# sigma_mix.net
KiCad netlist of a schematic drawn in EAGLE
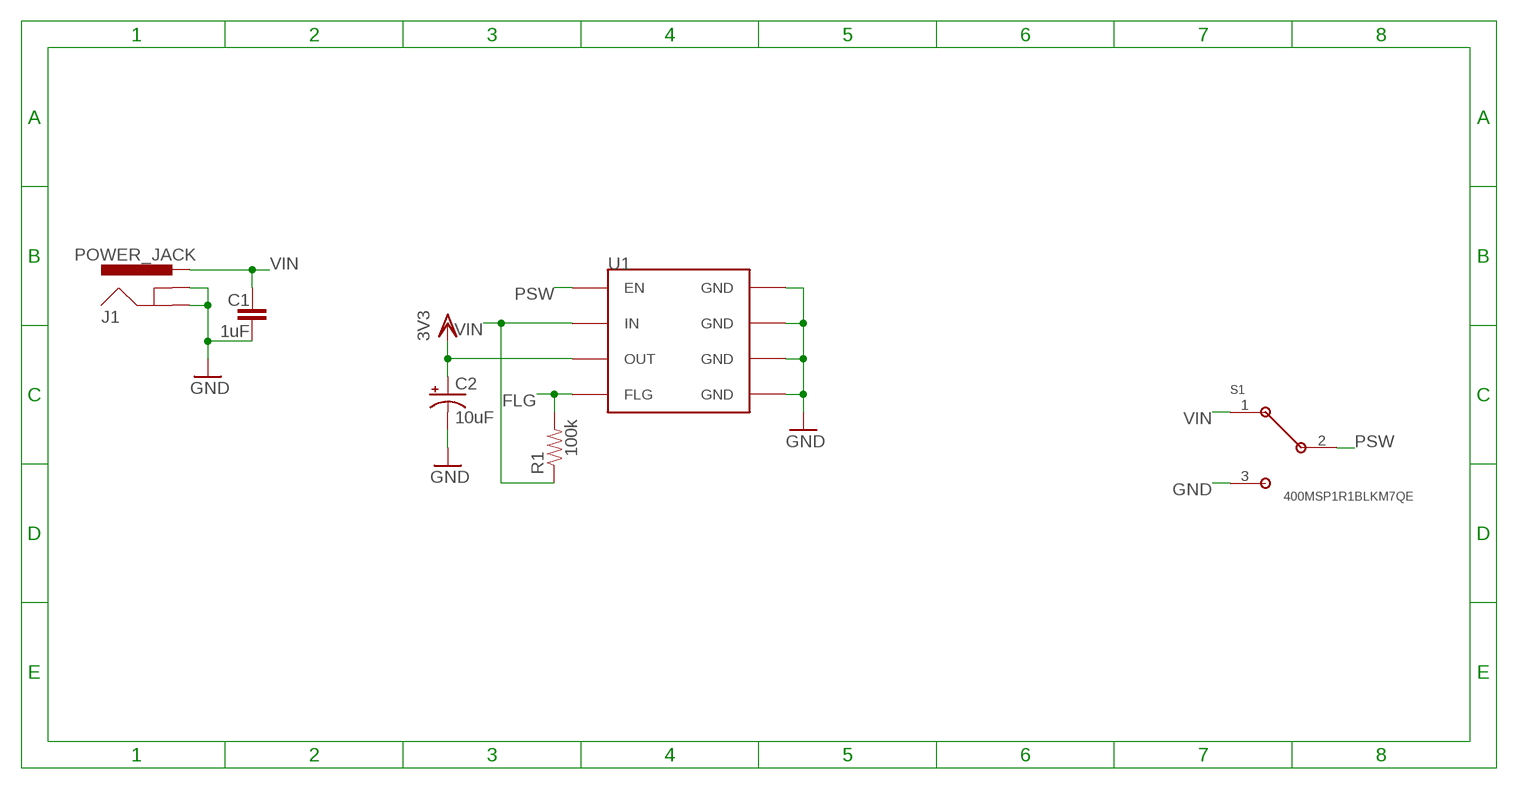
[diagram p0: schematic, sheet 1]
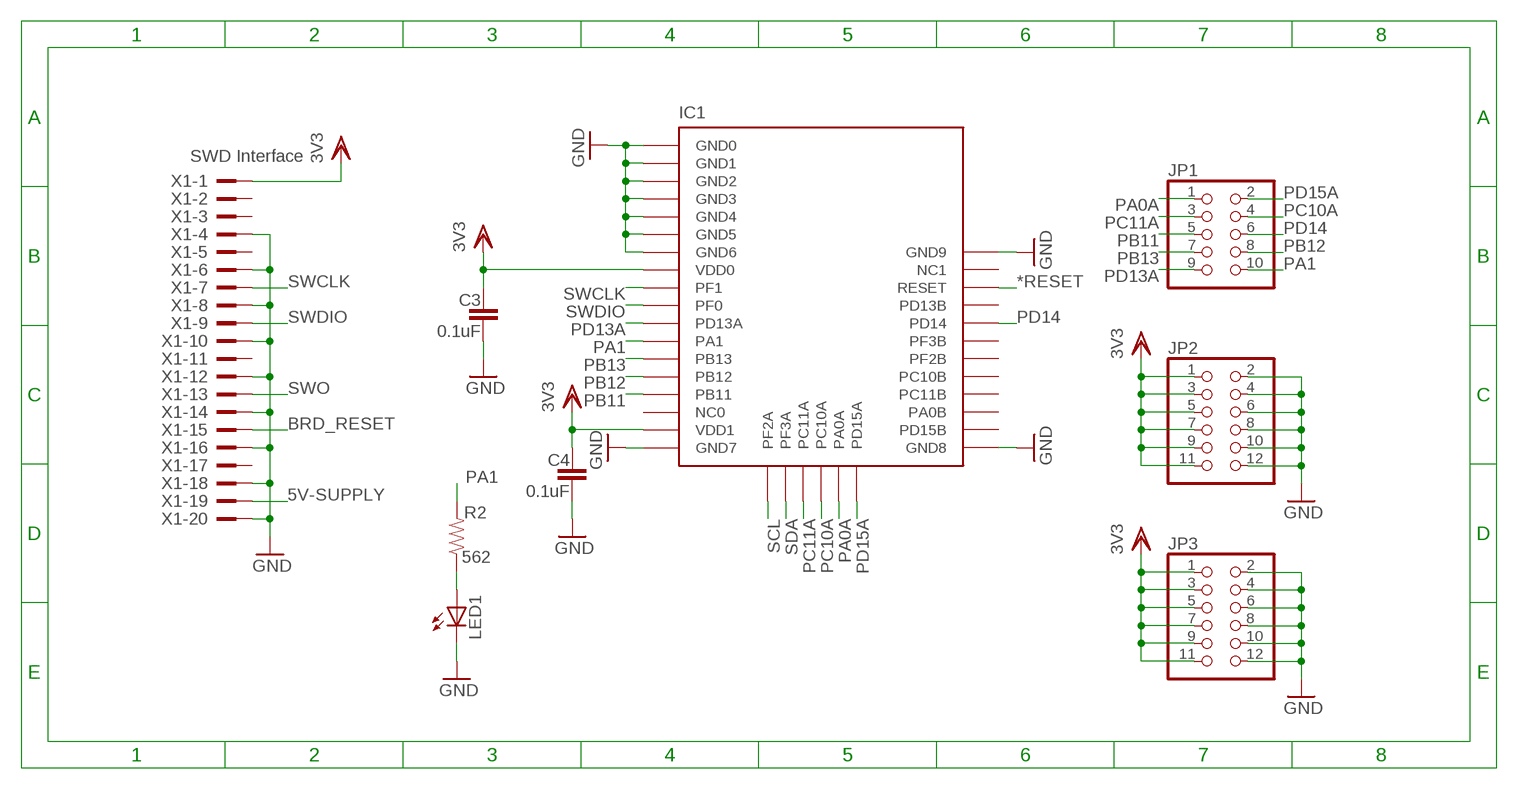
[diagram p1: schematic, sheet 2]
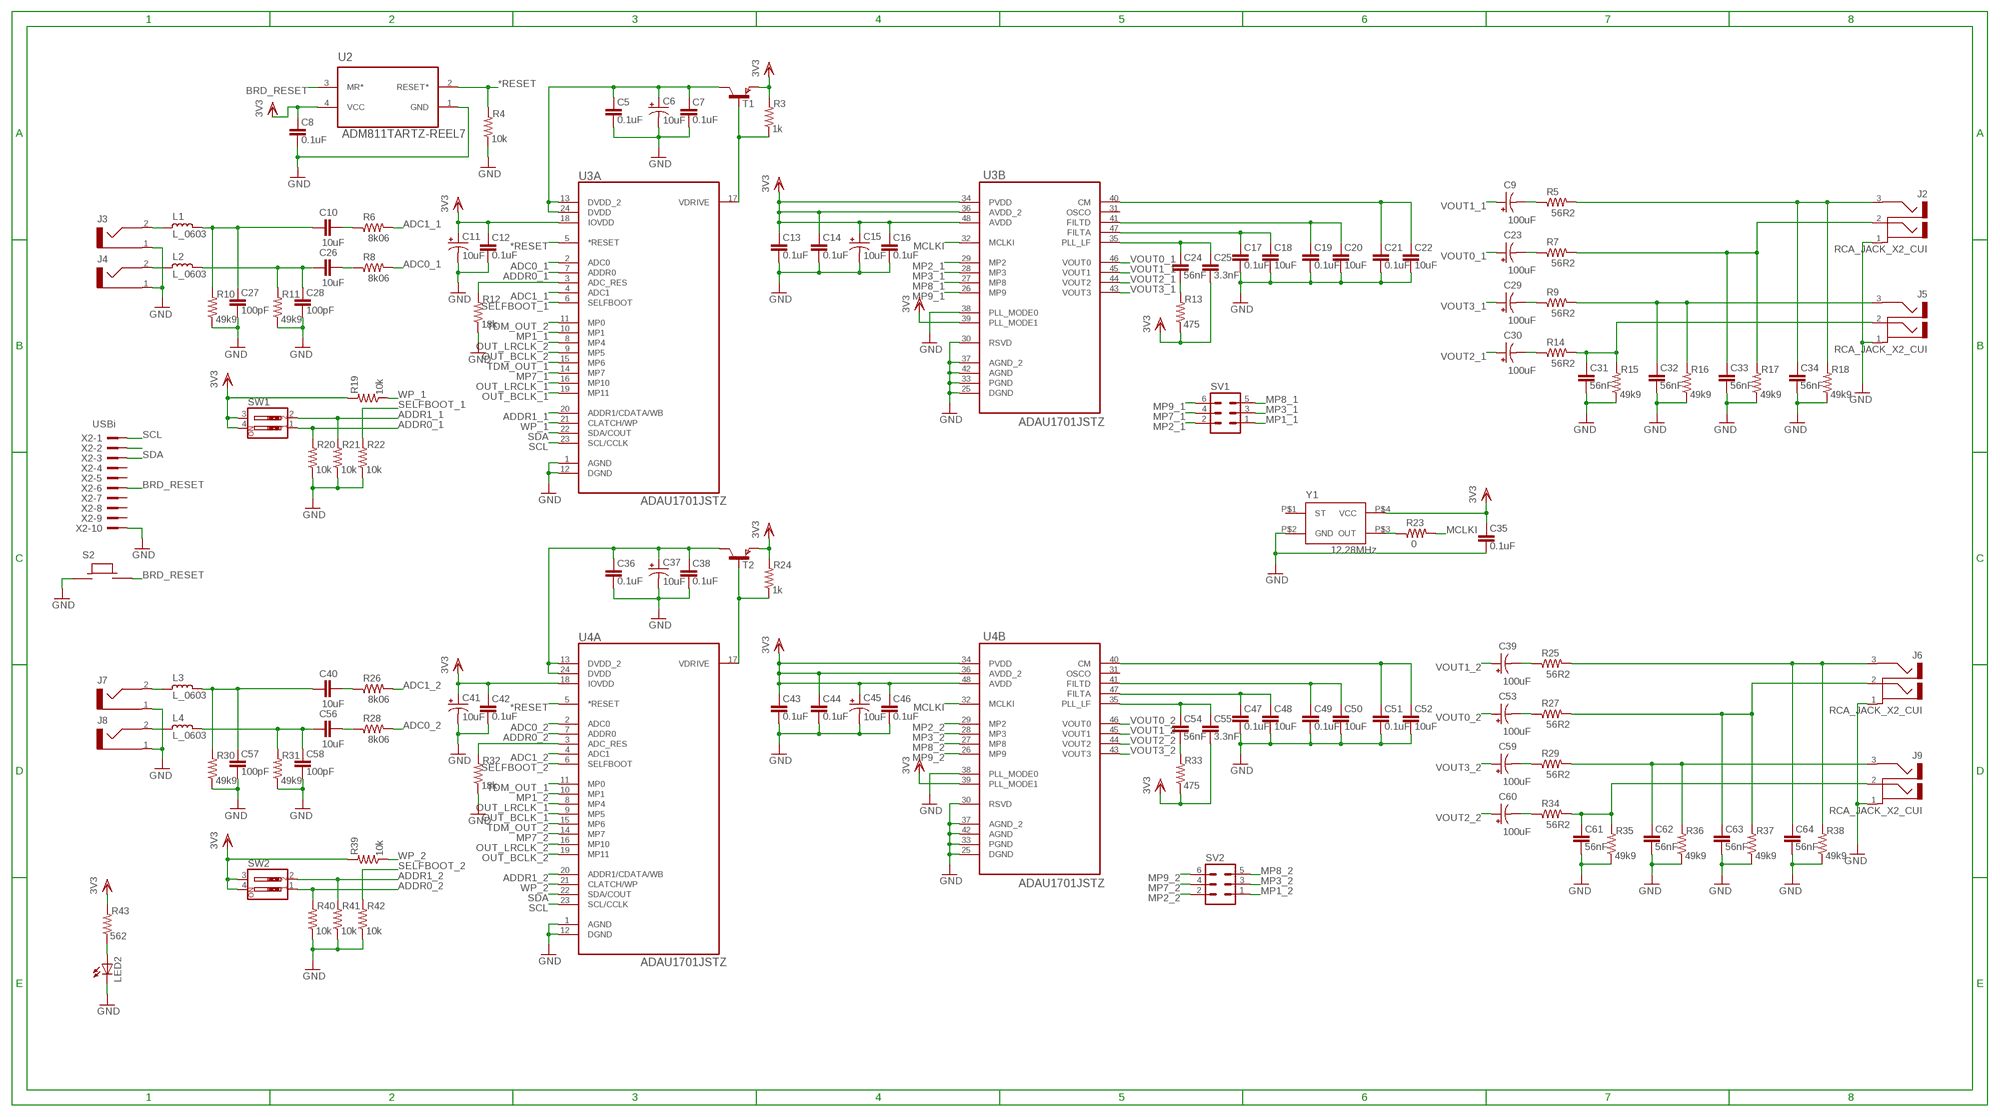
[diagram p2: schematic, sheet 3]

(export (version "E")
  (design (tool "Eeschema 10.0.6"))
  (components
    (comp (ref "C3")
      (value "0.1uF")
      (footprint "eagle-import:C2012")
      (libsource (lib "eagle-import") (part "C-EUC2012"))
    )
    (comp (ref "C4")
      (value "0.1uF")
      (footprint "eagle-import:C2012")
      (libsource (lib "eagle-import") (part "C-EUC2012"))
    )
    (comp (ref "IC1")
      (value "BGM113")
      (footprint "eagle-import:BLE113")
      (libsource (lib "eagle-import") (part "BGM113"))
    )
    (comp (ref "JP1")
      (value "PINHD-2X5")
      (footprint "eagle-import:2X05")
      (libsource (lib "eagle-import") (part "PINHD-2X5"))
    )
    (comp (ref "JP2")
      (value "PINHD-2X6")
      (footprint "eagle-import:2X06")
      (libsource (lib "eagle-import") (part "PINHD-2X6"))
    )
    (comp (ref "JP3")
      (value "PINHD-2X6")
      (footprint "eagle-import:2X06")
      (libsource (lib "eagle-import") (part "PINHD-2X6"))
    )
    (comp (ref "LED1")
      (value "LEDCHIPLED_1206")
      (footprint "eagle-import:CHIPLED_1206")
      (libsource (lib "eagle-import") (part "LEDCHIPLED_1206"))
    )
    (comp (ref "R2")
      (value "562")
      (footprint "eagle-import:0603-RES")
      (libsource (lib "eagle-import") (part "RESISTOR0603-RES"))
    )
    (comp (ref "X1")
      (value "SWD Interface")
      (footprint "eagle-import:PAK100_2500-20")
      (libsource (lib "eagle-import") (part "2520-"))
    )
    (comp (ref "C5")
      (value "0.1uF")
      (footprint "eagle-import:C2012")
      (libsource (lib "eagle-import") (part "C-EUC2012"))
    )
    (comp (ref "C6")
      (value "10uF")
      (footprint "eagle-import:R_2012-12R")
      (libsource (lib "eagle-import") (part "CPOL-USR/2012-12R"))
    )
    (comp (ref "C7")
      (value "0.1uF")
      (footprint "eagle-import:C2012")
      (libsource (lib "eagle-import") (part "C-EUC2012"))
    )
    (comp (ref "C8")
      (value "0.1uF")
      (footprint "eagle-import:C2012")
      (libsource (lib "eagle-import") (part "C-EUC2012"))
    )
    (comp (ref "C9")
      (value "100uF")
      (footprint "eagle-import:B_3528-21R")
      (libsource (lib "eagle-import") (part "CPOL-USB/3528-21R"))
    )
    (comp (ref "C10")
      (value "10uF")
      (footprint "eagle-import:C2012")
      (libsource (lib "eagle-import") (part "C-EUC2012"))
    )
    (comp (ref "C11")
      (value "10uF")
      (footprint "eagle-import:R_2012-12R")
      (libsource (lib "eagle-import") (part "CPOL-USR/2012-12R"))
    )
    (comp (ref "C12")
      (value "0.1uF")
      (footprint "eagle-import:C2012")
      (libsource (lib "eagle-import") (part "C-EUC2012"))
    )
    (comp (ref "C13")
      (value "0.1uF")
      (footprint "eagle-import:C2012")
      (libsource (lib "eagle-import") (part "C-EUC2012"))
    )
    (comp (ref "C14")
      (value "0.1uF")
      (footprint "eagle-import:C2012")
      (libsource (lib "eagle-import") (part "C-EUC2012"))
    )
    (comp (ref "C15")
      (value "10uF")
      (footprint "eagle-import:R_2012-12R")
      (libsource (lib "eagle-import") (part "CPOL-USR/2012-12R"))
    )
    (comp (ref "C16")
      (value "0.1uF")
      (footprint "eagle-import:C2012")
      (libsource (lib "eagle-import") (part "C-EUC2012"))
    )
    (comp (ref "C17")
      (value "0.1uF")
      (footprint "eagle-import:C2012")
      (libsource (lib "eagle-import") (part "C-EUC2012"))
    )
    (comp (ref "C18")
      (value "10uF")
      (footprint "eagle-import:C2012")
      (libsource (lib "eagle-import") (part "C-EUC2012"))
    )
    (comp (ref "C19")
      (value "0.1uF")
      (footprint "eagle-import:C2012")
      (libsource (lib "eagle-import") (part "C-EUC2012"))
    )
    (comp (ref "C20")
      (value "10uF")
      (footprint "eagle-import:C2012")
      (libsource (lib "eagle-import") (part "C-EUC2012"))
    )
    (comp (ref "C21")
      (value "0.1uF")
      (footprint "eagle-import:C2012")
      (libsource (lib "eagle-import") (part "C-EUC2012"))
    )
    (comp (ref "C22")
      (value "10uF")
      (footprint "eagle-import:C2012")
      (libsource (lib "eagle-import") (part "C-EUC2012"))
    )
    (comp (ref "C23")
      (value "100uF")
      (footprint "eagle-import:B_3528-21R")
      (libsource (lib "eagle-import") (part "CPOL-USB/3528-21R"))
    )
    (comp (ref "C24")
      (value "56nF")
      (footprint "eagle-import:C2012")
      (libsource (lib "eagle-import") (part "C-EUC2012"))
    )
    (comp (ref "C25")
      (value "3.3nF")
      (footprint "eagle-import:C2012")
      (libsource (lib "eagle-import") (part "C-EUC2012"))
    )
    (comp (ref "C26")
      (value "10uF")
      (footprint "eagle-import:C2012")
      (libsource (lib "eagle-import") (part "C-EUC2012"))
    )
    (comp (ref "C27")
      (value "100pF")
      (footprint "eagle-import:C2012")
      (libsource (lib "eagle-import") (part "C-EUC2012"))
    )
    (comp (ref "C28")
      (value "100pF")
      (footprint "eagle-import:C2012")
      (libsource (lib "eagle-import") (part "C-EUC2012"))
    )
    (comp (ref "C29")
      (value "100uF")
      (footprint "eagle-import:B_3528-21R")
      (libsource (lib "eagle-import") (part "CPOL-USB/3528-21R"))
    )
    (comp (ref "C30")
      (value "100uF")
      (footprint "eagle-import:B_3528-21R")
      (libsource (lib "eagle-import") (part "CPOL-USB/3528-21R"))
    )
    (comp (ref "C31")
      (value "56nF")
      (footprint "eagle-import:C2012")
      (libsource (lib "eagle-import") (part "C-EUC2012"))
    )
    (comp (ref "C32")
      (value "56nF")
      (footprint "eagle-import:C2012")
      (libsource (lib "eagle-import") (part "C-EUC2012"))
    )
    (comp (ref "C33")
      (value "56nF")
      (footprint "eagle-import:C2012")
      (libsource (lib "eagle-import") (part "C-EUC2012"))
    )
    (comp (ref "C34")
      (value "56nF")
      (footprint "eagle-import:C2012")
      (libsource (lib "eagle-import") (part "C-EUC2012"))
    )
    (comp (ref "C35")
      (value "0.1uF")
      (footprint "eagle-import:C2012")
      (libsource (lib "eagle-import") (part "C-EUC2012"))
    )
    (comp (ref "C36")
      (value "0.1uF")
      (footprint "eagle-import:C2012")
      (libsource (lib "eagle-import") (part "C-EUC2012"))
    )
    (comp (ref "C37")
      (value "10uF")
      (footprint "eagle-import:R_2012-12R")
      (libsource (lib "eagle-import") (part "CPOL-USR/2012-12R"))
    )
    (comp (ref "C38")
      (value "0.1uF")
      (footprint "eagle-import:C2012")
      (libsource (lib "eagle-import") (part "C-EUC2012"))
    )
    (comp (ref "C39")
      (value "100uF")
      (footprint "eagle-import:B_3528-21R")
      (libsource (lib "eagle-import") (part "CPOL-USB/3528-21R"))
    )
    (comp (ref "C40")
      (value "10uF")
      (footprint "eagle-import:C2012")
      (libsource (lib "eagle-import") (part "C-EUC2012"))
    )
    (comp (ref "C41")
      (value "10uF")
      (footprint "eagle-import:R_2012-12R")
      (libsource (lib "eagle-import") (part "CPOL-USR/2012-12R"))
    )
    (comp (ref "C42")
      (value "0.1uF")
      (footprint "eagle-import:C2012")
      (libsource (lib "eagle-import") (part "C-EUC2012"))
    )
    (comp (ref "C43")
      (value "0.1uF")
      (footprint "eagle-import:C2012")
      (libsource (lib "eagle-import") (part "C-EUC2012"))
    )
    (comp (ref "C44")
      (value "0.1uF")
      (footprint "eagle-import:C2012")
      (libsource (lib "eagle-import") (part "C-EUC2012"))
    )
    (comp (ref "C45")
      (value "10uF")
      (footprint "eagle-import:R_2012-12R")
      (libsource (lib "eagle-import") (part "CPOL-USR/2012-12R"))
    )
    (comp (ref "C46")
      (value "0.1uF")
      (footprint "eagle-import:C2012")
      (libsource (lib "eagle-import") (part "C-EUC2012"))
    )
    (comp (ref "C47")
      (value "0.1uF")
      (footprint "eagle-import:C2012")
      (libsource (lib "eagle-import") (part "C-EUC2012"))
    )
    (comp (ref "C48")
      (value "10uF")
      (footprint "eagle-import:C2012")
      (libsource (lib "eagle-import") (part "C-EUC2012"))
    )
    (comp (ref "C49")
      (value "0.1uF")
      (footprint "eagle-import:C2012")
      (libsource (lib "eagle-import") (part "C-EUC2012"))
    )
    (comp (ref "C50")
      (value "10uF")
      (footprint "eagle-import:C2012")
      (libsource (lib "eagle-import") (part "C-EUC2012"))
    )
    (comp (ref "C51")
      (value "0.1uF")
      (footprint "eagle-import:C2012")
      (libsource (lib "eagle-import") (part "C-EUC2012"))
    )
    (comp (ref "C52")
      (value "10uF")
      (footprint "eagle-import:C2012")
      (libsource (lib "eagle-import") (part "C-EUC2012"))
    )
    (comp (ref "C53")
      (value "100uF")
      (footprint "eagle-import:B_3528-21R")
      (libsource (lib "eagle-import") (part "CPOL-USB/3528-21R"))
    )
    (comp (ref "C54")
      (value "56nF")
      (footprint "eagle-import:C2012")
      (libsource (lib "eagle-import") (part "C-EUC2012"))
    )
    (comp (ref "C55")
      (value "3.3nF")
      (footprint "eagle-import:C2012")
      (libsource (lib "eagle-import") (part "C-EUC2012"))
    )
    (comp (ref "C56")
      (value "10uF")
      (footprint "eagle-import:C2012")
      (libsource (lib "eagle-import") (part "C-EUC2012"))
    )
    (comp (ref "C57")
      (value "100pF")
      (footprint "eagle-import:C2012")
      (libsource (lib "eagle-import") (part "C-EUC2012"))
    )
    (comp (ref "C58")
      (value "100pF")
      (footprint "eagle-import:C2012")
      (libsource (lib "eagle-import") (part "C-EUC2012"))
    )
    (comp (ref "C59")
      (value "100uF")
      (footprint "eagle-import:B_3528-21R")
      (libsource (lib "eagle-import") (part "CPOL-USB/3528-21R"))
    )
    (comp (ref "C60")
      (value "100uF")
      (footprint "eagle-import:B_3528-21R")
      (libsource (lib "eagle-import") (part "CPOL-USB/3528-21R"))
    )
    (comp (ref "C61")
      (value "56nF")
      (footprint "eagle-import:C2012")
      (libsource (lib "eagle-import") (part "C-EUC2012"))
    )
    (comp (ref "C62")
      (value "56nF")
      (footprint "eagle-import:C2012")
      (libsource (lib "eagle-import") (part "C-EUC2012"))
    )
    (comp (ref "C63")
      (value "56nF")
      (footprint "eagle-import:C2012")
      (libsource (lib "eagle-import") (part "C-EUC2012"))
    )
    (comp (ref "C64")
      (value "56nF")
      (footprint "eagle-import:C2012")
      (libsource (lib "eagle-import") (part "C-EUC2012"))
    )
    (comp (ref "J2")
      (value "RCA_JACK_X2_CUI")
      (footprint "eagle-import:RCA_JACK_X2_CUI")
      (libsource (lib "eagle-import") (part "RCA_JACK_X2_CUI"))
    )
    (comp (ref "J3")
      (value "RCA_JACK_CUI")
      (footprint "eagle-import:RCA_JACK_CUI")
      (libsource (lib "eagle-import") (part "RCA_JACK_CUI"))
    )
    (comp (ref "J4")
      (value "RCA_JACK_CUI")
      (footprint "eagle-import:RCA_JACK_CUI")
      (libsource (lib "eagle-import") (part "RCA_JACK_CUI"))
    )
    (comp (ref "J5")
      (value "RCA_JACK_X2_CUI")
      (footprint "eagle-import:RCA_JACK_X2_CUI")
      (libsource (lib "eagle-import") (part "RCA_JACK_X2_CUI"))
    )
    (comp (ref "J6")
      (value "RCA_JACK_X2_CUI")
      (footprint "eagle-import:RCA_JACK_X2_CUI")
      (libsource (lib "eagle-import") (part "RCA_JACK_X2_CUI"))
    )
    (comp (ref "J7")
      (value "RCA_JACK_CUI")
      (footprint "eagle-import:RCA_JACK_CUI")
      (libsource (lib "eagle-import") (part "RCA_JACK_CUI"))
    )
    (comp (ref "J8")
      (value "RCA_JACK_CUI")
      (footprint "eagle-import:RCA_JACK_CUI")
      (libsource (lib "eagle-import") (part "RCA_JACK_CUI"))
    )
    (comp (ref "J9")
      (value "RCA_JACK_X2_CUI")
      (footprint "eagle-import:RCA_JACK_X2_CUI")
      (libsource (lib "eagle-import") (part "RCA_JACK_X2_CUI"))
    )
    (comp (ref "L1")
      (value "L_0603")
      (footprint "eagle-import:L0603")
      (libsource (lib "eagle-import") (part "L_0603"))
    )
    (comp (ref "L2")
      (value "L_0603")
      (footprint "eagle-import:L0603")
      (libsource (lib "eagle-import") (part "L_0603"))
    )
    (comp (ref "L3")
      (value "L_0603")
      (footprint "eagle-import:L0603")
      (libsource (lib "eagle-import") (part "L_0603"))
    )
    (comp (ref "L4")
      (value "L_0603")
      (footprint "eagle-import:L0603")
      (libsource (lib "eagle-import") (part "L_0603"))
    )
    (comp (ref "LED2")
      (value "LEDCHIPLED_1206")
      (footprint "eagle-import:CHIPLED_1206")
      (libsource (lib "eagle-import") (part "LEDCHIPLED_1206"))
    )
    (comp (ref "R3")
      (value "1k")
      (footprint "eagle-import:0603-RES")
      (libsource (lib "eagle-import") (part "RESISTOR0603-RES"))
    )
    (comp (ref "R4")
      (value "10k")
      (footprint "eagle-import:0603-RES")
      (libsource (lib "eagle-import") (part "RESISTOR0603-RES"))
    )
    (comp (ref "R5")
      (value "56R2")
      (footprint "eagle-import:0603-RES")
      (libsource (lib "eagle-import") (part "RESISTOR0603-RES"))
    )
    (comp (ref "R6")
      (value "8k06")
      (footprint "eagle-import:0603-RES")
      (libsource (lib "eagle-import") (part "RESISTOR0603-RES"))
    )
    (comp (ref "R7")
      (value "56R2")
      (footprint "eagle-import:0603-RES")
      (libsource (lib "eagle-import") (part "RESISTOR0603-RES"))
    )
    (comp (ref "R8")
      (value "8k06")
      (footprint "eagle-import:0603-RES")
      (libsource (lib "eagle-import") (part "RESISTOR0603-RES"))
    )
    (comp (ref "R9")
      (value "56R2")
      (footprint "eagle-import:0603-RES")
      (libsource (lib "eagle-import") (part "RESISTOR0603-RES"))
    )
    (comp (ref "R10")
      (value "49k9")
      (footprint "eagle-import:0603-RES")
      (libsource (lib "eagle-import") (part "RESISTOR0603-RES"))
    )
    (comp (ref "R11")
      (value "49k9")
      (footprint "eagle-import:0603-RES")
      (libsource (lib "eagle-import") (part "RESISTOR0603-RES"))
    )
    (comp (ref "R12")
      (value "18k")
      (footprint "eagle-import:0603-RES")
      (libsource (lib "eagle-import") (part "RESISTOR0603-RES"))
    )
    (comp (ref "R13")
      (value "475")
      (footprint "eagle-import:0603-RES")
      (libsource (lib "eagle-import") (part "RESISTOR0603-RES"))
    )
    (comp (ref "R14")
      (value "56R2")
      (footprint "eagle-import:0603-RES")
      (libsource (lib "eagle-import") (part "RESISTOR0603-RES"))
    )
    (comp (ref "R15")
      (value "49k9")
      (footprint "eagle-import:0603-RES")
      (libsource (lib "eagle-import") (part "RESISTOR0603-RES"))
    )
    (comp (ref "R16")
      (value "49k9")
      (footprint "eagle-import:0603-RES")
      (libsource (lib "eagle-import") (part "RESISTOR0603-RES"))
    )
    (comp (ref "R17")
      (value "49k9")
      (footprint "eagle-import:0603-RES")
      (libsource (lib "eagle-import") (part "RESISTOR0603-RES"))
    )
    (comp (ref "R18")
      (value "49k9")
      (footprint "eagle-import:0603-RES")
      (libsource (lib "eagle-import") (part "RESISTOR0603-RES"))
    )
    (comp (ref "R19")
      (value "10k")
      (footprint "eagle-import:0603-RES")
      (libsource (lib "eagle-import") (part "RESISTOR0603-RES"))
    )
    (comp (ref "R20")
      (value "10k")
      (footprint "eagle-import:0603-RES")
      (libsource (lib "eagle-import") (part "RESISTOR0603-RES"))
    )
    (comp (ref "R21")
      (value "10k")
      (footprint "eagle-import:0603-RES")
      (libsource (lib "eagle-import") (part "RESISTOR0603-RES"))
    )
    (comp (ref "R22")
      (value "10k")
      (footprint "eagle-import:0603-RES")
      (libsource (lib "eagle-import") (part "RESISTOR0603-RES"))
    )
    (comp (ref "R23")
      (value "0")
      (footprint "eagle-import:0603-RES")
      (libsource (lib "eagle-import") (part "RESISTOR0603-RES"))
    )
    (comp (ref "R24")
      (value "1k")
      (footprint "eagle-import:0603-RES")
      (libsource (lib "eagle-import") (part "RESISTOR0603-RES"))
    )
    (comp (ref "R25")
      (value "56R2")
      (footprint "eagle-import:0603-RES")
      (libsource (lib "eagle-import") (part "RESISTOR0603-RES"))
    )
    (comp (ref "R26")
      (value "8k06")
      (footprint "eagle-import:0603-RES")
      (libsource (lib "eagle-import") (part "RESISTOR0603-RES"))
    )
    (comp (ref "R27")
      (value "56R2")
      (footprint "eagle-import:0603-RES")
      (libsource (lib "eagle-import") (part "RESISTOR0603-RES"))
    )
    (comp (ref "R28")
      (value "8k06")
      (footprint "eagle-import:0603-RES")
      (libsource (lib "eagle-import") (part "RESISTOR0603-RES"))
    )
    (comp (ref "R29")
      (value "56R2")
      (footprint "eagle-import:0603-RES")
      (libsource (lib "eagle-import") (part "RESISTOR0603-RES"))
    )
    (comp (ref "R30")
      (value "49k9")
      (footprint "eagle-import:0603-RES")
      (libsource (lib "eagle-import") (part "RESISTOR0603-RES"))
    )
    (comp (ref "R31")
      (value "49k9")
      (footprint "eagle-import:0603-RES")
      (libsource (lib "eagle-import") (part "RESISTOR0603-RES"))
    )
    (comp (ref "R32")
      (value "18k")
      (footprint "eagle-import:0603-RES")
      (libsource (lib "eagle-import") (part "RESISTOR0603-RES"))
    )
    (comp (ref "R33")
      (value "475")
      (footprint "eagle-import:0603-RES")
      (libsource (lib "eagle-import") (part "RESISTOR0603-RES"))
    )
    (comp (ref "R34")
      (value "56R2")
      (footprint "eagle-import:0603-RES")
      (libsource (lib "eagle-import") (part "RESISTOR0603-RES"))
    )
    (comp (ref "R35")
      (value "49k9")
      (footprint "eagle-import:0603-RES")
      (libsource (lib "eagle-import") (part "RESISTOR0603-RES"))
    )
    (comp (ref "R36")
      (value "49k9")
      (footprint "eagle-import:0603-RES")
      (libsource (lib "eagle-import") (part "RESISTOR0603-RES"))
    )
    (comp (ref "R37")
      (value "49k9")
      (footprint "eagle-import:0603-RES")
      (libsource (lib "eagle-import") (part "RESISTOR0603-RES"))
    )
    (comp (ref "R38")
      (value "49k9")
      (footprint "eagle-import:0603-RES")
      (libsource (lib "eagle-import") (part "RESISTOR0603-RES"))
    )
    (comp (ref "R39")
      (value "10k")
      (footprint "eagle-import:0603-RES")
      (libsource (lib "eagle-import") (part "RESISTOR0603-RES"))
    )
    (comp (ref "R40")
      (value "10k")
      (footprint "eagle-import:0603-RES")
      (libsource (lib "eagle-import") (part "RESISTOR0603-RES"))
    )
    (comp (ref "R41")
      (value "10k")
      (footprint "eagle-import:0603-RES")
      (libsource (lib "eagle-import") (part "RESISTOR0603-RES"))
    )
    (comp (ref "R42")
      (value "10k")
      (footprint "eagle-import:0603-RES")
      (libsource (lib "eagle-import") (part "RESISTOR0603-RES"))
    )
    (comp (ref "R43")
      (value "562")
      (footprint "eagle-import:0603-RES")
      (libsource (lib "eagle-import") (part "RESISTOR0603-RES"))
    )
    (comp (ref "S2")
      (value "OMRON_B3M")
      (footprint "eagle-import:OMRON_B3M")
      (libsource (lib "eagle-import") (part "OMRON_B3M"))
    )
    (comp (ref "SV1")
      (value "MA03-2")
      (footprint "eagle-import:MA03-2")
      (libsource (lib "eagle-import") (part "MA03-2"))
    )
    (comp (ref "SV2")
      (value "MA03-2")
      (footprint "eagle-import:MA03-2")
      (libsource (lib "eagle-import") (part "MA03-2"))
    )
    (comp (ref "SW1")
      (value "SW_DIP-2")
      (footprint "eagle-import:EDG-02")
      (libsource (lib "eagle-import") (part "SW_DIP-2"))
    )
    (comp (ref "SW2")
      (value "SW_DIP-2")
      (footprint "eagle-import:EDG-02")
      (libsource (lib "eagle-import") (part "SW_DIP-2"))
    )
    (comp (ref "T1")
      (value "PNPSOT23")
      (footprint "eagle-import:SOT-23")
      (fields (field (name "MPN") "DSS20200L-7"))
      (libsource (lib "eagle-import") (part "PNPSOT23"))
    )
    (comp (ref "T2")
      (value "PNPSOT23")
      (footprint "eagle-import:SOT-23")
      (fields (field (name "MPN") "DSS20200L-7"))
      (libsource (lib "eagle-import") (part "PNPSOT23"))
    )
    (comp (ref "U2")
      (value "ADM811TARTZ-REEL7")
      (footprint "eagle-import:SOT143P290X130-4N")
      (libsource (lib "eagle-import") (part "ADM811TARTZ-REEL7"))
    )
    (comp (ref "U3")
      (value "ADAU1701JSTZ")
      (footprint "eagle-import:QFP50P900X900X160-48N")
      (libsource (lib "eagle-import") (part "ADAU1701JSTZ"))
    )
    (comp (ref "U4")
      (value "ADAU1701JSTZ")
      (footprint "eagle-import:QFP50P900X900X160-48N")
      (libsource (lib "eagle-import") (part "ADAU1701JSTZ"))
    )
    (comp (ref "X2")
      (value "USBi")
      (footprint "eagle-import:PAK100_2500-10")
      (fields (field (name "MF") "3M") (field (name "MPN") "2510-6002UB"))
      (libsource (lib "eagle-import") (part "2510-"))
    )
    (comp (ref "Y1")
      (value "12.28MHz")
      (footprint "eagle-import:SG-210")
      (libsource (lib "eagle-import") (part "XTAL-OSC"))
    )
    (comp (ref "C1")
      (value "1uF")
      (footprint "eagle-import:C2012")
      (libsource (lib "eagle-import") (part "C-EUC2012"))
    )
    (comp (ref "C2")
      (value "10uF")
      (footprint "eagle-import:R_2012-12R")
      (libsource (lib "eagle-import") (part "CPOL-USR/2012-12R"))
    )
    (comp (ref "J1")
      (value "POWER_JACK")
      (footprint "eagle-import:POWER_JACK_PTH_LOCK")
      (libsource (lib "eagle-import") (part "POWER_JACKPTH_LOCK"))
    )
    (comp (ref "R1")
      (value "100k")
      (footprint "eagle-import:0603-RES")
      (libsource (lib "eagle-import") (part "RESISTOR0603-RES"))
    )
    (comp (ref "S1")
      (value "400MSP1R1BLKM7QE")
      (footprint "eagle-import:400MSP1R1BLKM7QE")
      (libsource (lib "eagle-import") (part "400MSP1R1BLKM7QE"))
    )
    (comp (ref "U1")
      (value "MIC39100")
      (footprint "eagle-import:SOIC8")
      (libsource (lib "eagle-import") (part "MIC39100"))
    )
  )
  (nets
    (net (code "1") (name "*RESET") (class "Default")
      (node (ref "IC1") (pin "P$34") (pinfunction "RESET_P$34") (pintype "input"))
      (node (ref "R4") (pin "2") (pinfunction "2_2") (pintype "passive"))
      (node (ref "U2") (pin "2") (pinfunction "RESET*_2") (pintype "passive"))
      (node (ref "U3") (pin "5") (pinfunction "*RESET_5") (pintype "input"))
      (node (ref "U4") (pin "5") (pinfunction "*RESET_5") (pintype "input"))
    )
    (net (code "2") (name "5V-SUPPLY") (class "Default")
      (node (ref "X1") (pin "19") (pinfunction "KL_19") (pintype "passive"))
    )
    (net (code "3") (name "ADC0_1") (class "Default")
      (node (ref "R8") (pin "2") (pinfunction "2_2") (pintype "passive"))
      (node (ref "U3") (pin "2") (pinfunction "ADC0_2") (pintype "input"))
    )
    (net (code "4") (name "ADC0_2") (class "Default")
      (node (ref "R28") (pin "2") (pinfunction "2_2") (pintype "passive"))
      (node (ref "U4") (pin "2") (pinfunction "ADC0_2") (pintype "input"))
    )
    (net (code "5") (name "ADC1_1") (class "Default")
      (node (ref "R6") (pin "2") (pinfunction "2_2") (pintype "passive"))
      (node (ref "U3") (pin "4") (pinfunction "ADC1_4") (pintype "input"))
    )
    (net (code "6") (name "ADC1_2") (class "Default")
      (node (ref "R26") (pin "2") (pinfunction "2_2") (pintype "passive"))
      (node (ref "U4") (pin "4") (pinfunction "ADC1_4") (pintype "input"))
    )
    (net (code "7") (name "ADDR0_1") (class "Default")
      (node (ref "R20") (pin "2") (pinfunction "2_2") (pintype "passive"))
      (node (ref "SW1") (pin "1") (pinfunction "1_1") (pintype "passive"))
      (node (ref "U3") (pin "7") (pinfunction "ADDR0_7") (pintype "input"))
    )
    (net (code "8") (name "ADDR0_2") (class "Default")
      (node (ref "R40") (pin "2") (pinfunction "2_2") (pintype "passive"))
      (node (ref "SW2") (pin "1") (pinfunction "1_1") (pintype "passive"))
      (node (ref "U4") (pin "7") (pinfunction "ADDR0_7") (pintype "input"))
    )
    (net (code "9") (name "ADDR1_1") (class "Default")
      (node (ref "R21") (pin "2") (pinfunction "2_2") (pintype "passive"))
      (node (ref "SW1") (pin "2") (pinfunction "2_2") (pintype "passive"))
      (node (ref "U3") (pin "20") (pinfunction "ADDR1/CDATA/WB_20") (pintype "input"))
    )
    (net (code "10") (name "ADDR1_2") (class "Default")
      (node (ref "R41") (pin "2") (pinfunction "2_2") (pintype "passive"))
      (node (ref "SW2") (pin "2") (pinfunction "2_2") (pintype "passive"))
      (node (ref "U4") (pin "20") (pinfunction "ADDR1/CDATA/WB_20") (pintype "input"))
    )
    (net (code "11") (name "BRD_RESET") (class "Default")
      (node (ref "S2") (pin "P$2") (pinfunction "P$2_P$2") (pintype "bidirectional"))
      (node (ref "U2") (pin "3") (pinfunction "MR*_3") (pintype "passive"))
      (node (ref "X1") (pin "15") (pinfunction "KL_15") (pintype "passive"))
      (node (ref "X2") (pin "6") (pinfunction "KL_6") (pintype "passive"))
    )
    (net (code "12") (name "FLG") (class "Default")
      (node (ref "R1") (pin "2") (pinfunction "2_2") (pintype "passive"))
      (node (ref "U1") (pin "4") (pinfunction "FLG_4") (pintype "output"))
    )
    (net (code "13") (name "GND") (class "Default")
      (node (ref "C1") (pin "2") (pinfunction "2_2") (pintype "passive"))
      (node (ref "C11") (pin "-") (pinfunction "-_-") (pintype "passive"))
      (node (ref "C12") (pin "2") (pinfunction "2_2") (pintype "passive"))
      (node (ref "C13") (pin "2") (pinfunction "2_2") (pintype "passive"))
      (node (ref "C14") (pin "2") (pinfunction "2_2") (pintype "passive"))
      (node (ref "C15") (pin "-") (pinfunction "-_-") (pintype "passive"))
      (node (ref "C16") (pin "2") (pinfunction "2_2") (pintype "passive"))
      (node (ref "C17") (pin "2") (pinfunction "2_2") (pintype "passive"))
      (node (ref "C18") (pin "2") (pinfunction "2_2") (pintype "passive"))
      (node (ref "C19") (pin "2") (pinfunction "2_2") (pintype "passive"))
      (node (ref "C2") (pin "-") (pinfunction "-_-") (pintype "passive"))
      (node (ref "C20") (pin "2") (pinfunction "2_2") (pintype "passive"))
      (node (ref "C21") (pin "2") (pinfunction "2_2") (pintype "passive"))
      (node (ref "C22") (pin "2") (pinfunction "2_2") (pintype "passive"))
      (node (ref "C27") (pin "2") (pinfunction "2_2") (pintype "passive"))
      (node (ref "C28") (pin "2") (pinfunction "2_2") (pintype "passive"))
      (node (ref "C3") (pin "2") (pinfunction "2_2") (pintype "passive"))
      (node (ref "C31") (pin "2") (pinfunction "2_2") (pintype "passive"))
      (node (ref "C32") (pin "2") (pinfunction "2_2") (pintype "passive"))
      (node (ref "C33") (pin "2") (pinfunction "2_2") (pintype "passive"))
      (node (ref "C34") (pin "2") (pinfunction "2_2") (pintype "passive"))
      (node (ref "C35") (pin "2") (pinfunction "2_2") (pintype "passive"))
      (node (ref "C36") (pin "2") (pinfunction "2_2") (pintype "passive"))
      (node (ref "C37") (pin "-") (pinfunction "-_-") (pintype "passive"))
      (node (ref "C38") (pin "2") (pinfunction "2_2") (pintype "passive"))
      (node (ref "C4") (pin "2") (pinfunction "2_2") (pintype "passive"))
      (node (ref "C41") (pin "-") (pinfunction "-_-") (pintype "passive"))
      (node (ref "C42") (pin "2") (pinfunction "2_2") (pintype "passive"))
      (node (ref "C43") (pin "2") (pinfunction "2_2") (pintype "passive"))
      (node (ref "C44") (pin "2") (pinfunction "2_2") (pintype "passive"))
      (node (ref "C45") (pin "-") (pinfunction "-_-") (pintype "passive"))
      (node (ref "C46") (pin "2") (pinfunction "2_2") (pintype "passive"))
      (node (ref "C47") (pin "2") (pinfunction "2_2") (pintype "passive"))
      (node (ref "C48") (pin "2") (pinfunction "2_2") (pintype "passive"))
      (node (ref "C49") (pin "2") (pinfunction "2_2") (pintype "passive"))
      (node (ref "C5") (pin "2") (pinfunction "2_2") (pintype "passive"))
      (node (ref "C50") (pin "2") (pinfunction "2_2") (pintype "passive"))
      (node (ref "C51") (pin "2") (pinfunction "2_2") (pintype "passive"))
      (node (ref "C52") (pin "2") (pinfunction "2_2") (pintype "passive"))
      (node (ref "C57") (pin "2") (pinfunction "2_2") (pintype "passive"))
      (node (ref "C58") (pin "2") (pinfunction "2_2") (pintype "passive"))
      (node (ref "C6") (pin "-") (pinfunction "-_-") (pintype "passive"))
      (node (ref "C61") (pin "2") (pinfunction "2_2") (pintype "passive"))
      (node (ref "C62") (pin "2") (pinfunction "2_2") (pintype "passive"))
      (node (ref "C63") (pin "2") (pinfunction "2_2") (pintype "passive"))
      (node (ref "C64") (pin "2") (pinfunction "2_2") (pintype "passive"))
      (node (ref "C7") (pin "2") (pinfunction "2_2") (pintype "passive"))
      (node (ref "C8") (pin "2") (pinfunction "2_2") (pintype "passive"))
      (node (ref "IC1") (pin "P$1") (pinfunction "GND0_P$1") (pintype "power_in"))
      (node (ref "IC1") (pin "P$18") (pinfunction "GND7_P$18") (pintype "power_in"))
      (node (ref "IC1") (pin "P$2") (pinfunction "GND1_P$2") (pintype "power_in"))
      (node (ref "IC1") (pin "P$25") (pinfunction "GND8_P$25") (pintype "power_in"))
      (node (ref "IC1") (pin "P$3") (pinfunction "GND2_P$3") (pintype "power_in"))
      (node (ref "IC1") (pin "P$36") (pinfunction "GND9_P$36") (pintype "power_in"))
      (node (ref "IC1") (pin "P$4") (pinfunction "GND3_P$4") (pintype "power_in"))
      (node (ref "IC1") (pin "P$5") (pinfunction "GND4_P$5") (pintype "power_in"))
      (node (ref "IC1") (pin "P$6") (pinfunction "GND5_P$6") (pintype "power_in"))
      (node (ref "IC1") (pin "P$7") (pinfunction "GND6_P$7") (pintype "power_in"))
      (node (ref "J1") (pin "GND") (pinfunction "GND_GND") (pintype "bidirectional"))
      (node (ref "J1") (pin "GNDBREAK") (pinfunction "GNDBREAK_GNDBREAK") (pintype "bidirectional"))
      (node (ref "J2") (pin "1") (pinfunction "1_1") (pintype "power_in"))
      (node (ref "J3") (pin "1") (pinfunction "1_1") (pintype "bidirectional"))
      (node (ref "J4") (pin "1") (pinfunction "1_1") (pintype "bidirectional"))
      (node (ref "J5") (pin "1") (pinfunction "1_1") (pintype "power_in"))
      (node (ref "J6") (pin "1") (pinfunction "1_1") (pintype "power_in"))
      (node (ref "J7") (pin "1") (pinfunction "1_1") (pintype "bidirectional"))
      (node (ref "J8") (pin "1") (pinfunction "1_1") (pintype "bidirectional"))
      (node (ref "J9") (pin "1") (pinfunction "1_1") (pintype "power_in"))
      (node (ref "JP2") (pin "10") (pinfunction "10_10") (pintype "passive"))
      (node (ref "JP2") (pin "12") (pinfunction "12_12") (pintype "passive"))
      (node (ref "JP2") (pin "2") (pinfunction "2_2") (pintype "passive"))
      (node (ref "JP2") (pin "4") (pinfunction "4_4") (pintype "passive"))
      (node (ref "JP2") (pin "6") (pinfunction "6_6") (pintype "passive"))
      (node (ref "JP2") (pin "8") (pinfunction "8_8") (pintype "passive"))
      (node (ref "JP3") (pin "10") (pinfunction "10_10") (pintype "passive"))
      (node (ref "JP3") (pin "12") (pinfunction "12_12") (pintype "passive"))
      (node (ref "JP3") (pin "2") (pinfunction "2_2") (pintype "passive"))
      (node (ref "JP3") (pin "4") (pinfunction "4_4") (pintype "passive"))
      (node (ref "JP3") (pin "6") (pinfunction "6_6") (pintype "passive"))
      (node (ref "JP3") (pin "8") (pinfunction "8_8") (pintype "passive"))
      (node (ref "LED1") (pin "C") (pinfunction "C_C") (pintype "passive"))
      (node (ref "LED2") (pin "C") (pinfunction "C_C") (pintype "passive"))
      (node (ref "R10") (pin "1") (pinfunction "1_1") (pintype "passive"))
      (node (ref "R11") (pin "1") (pinfunction "1_1") (pintype "passive"))
      (node (ref "R12") (pin "1") (pinfunction "1_1") (pintype "passive"))
      (node (ref "R15") (pin "1") (pinfunction "1_1") (pintype "passive"))
      (node (ref "R16") (pin "1") (pinfunction "1_1") (pintype "passive"))
      (node (ref "R17") (pin "1") (pinfunction "1_1") (pintype "passive"))
      (node (ref "R18") (pin "1") (pinfunction "1_1") (pintype "passive"))
      (node (ref "R20") (pin "1") (pinfunction "1_1") (pintype "passive"))
      (node (ref "R21") (pin "1") (pinfunction "1_1") (pintype "passive"))
      (node (ref "R22") (pin "1") (pinfunction "1_1") (pintype "passive"))
      (node (ref "R30") (pin "1") (pinfunction "1_1") (pintype "passive"))
      (node (ref "R31") (pin "1") (pinfunction "1_1") (pintype "passive"))
      (node (ref "R32") (pin "1") (pinfunction "1_1") (pintype "passive"))
      (node (ref "R35") (pin "1") (pinfunction "1_1") (pintype "passive"))
      (node (ref "R36") (pin "1") (pinfunction "1_1") (pintype "passive"))
      (node (ref "R37") (pin "1") (pinfunction "1_1") (pintype "passive"))
      (node (ref "R38") (pin "1") (pinfunction "1_1") (pintype "passive"))
      (node (ref "R4") (pin "1") (pinfunction "1_1") (pintype "passive"))
      (node (ref "R40") (pin "1") (pinfunction "1_1") (pintype "passive"))
      (node (ref "R41") (pin "1") (pinfunction "1_1") (pintype "passive"))
      (node (ref "R42") (pin "1") (pinfunction "1_1") (pintype "passive"))
      (node (ref "S1") (pin "3") (pinfunction "3_3") (pintype "bidirectional"))
      (node (ref "S2") (pin "P$1") (pinfunction "P$1_P$1") (pintype "bidirectional"))
      (node (ref "U1") (pin "5") (pinfunction "GND_5") (pintype "power_in"))
      (node (ref "U1") (pin "6") (pinfunction "GND_6") (pintype "power_in"))
      (node (ref "U1") (pin "7") (pinfunction "GND_7") (pintype "power_in"))
      (node (ref "U1") (pin "8") (pinfunction "GND_8") (pintype "power_in"))
      (node (ref "U2") (pin "1") (pinfunction "GND_1") (pintype "passive"))
      (node (ref "U3") (pin "1") (pinfunction "AGND_1") (pintype "passive"))
      (node (ref "U3") (pin "12") (pinfunction "DGND_12") (pintype "passive"))
      (node (ref "U3") (pin "25") (pinfunction "DGND_25") (pintype "passive"))
      (node (ref "U3") (pin "30") (pinfunction "RSVD_30") (pintype "passive"))
      (node (ref "U3") (pin "33") (pinfunction "PGND_33") (pintype "passive"))
      (node (ref "U3") (pin "37") (pinfunction "AGND_2_37") (pintype "passive"))
      (node (ref "U3") (pin "38") (pinfunction "PLL_MODE0_38") (pintype "input"))
      (node (ref "U3") (pin "42") (pinfunction "AGND_42") (pintype "passive"))
      (node (ref "U4") (pin "1") (pinfunction "AGND_1") (pintype "passive"))
      (node (ref "U4") (pin "12") (pinfunction "DGND_12") (pintype "passive"))
      (node (ref "U4") (pin "25") (pinfunction "DGND_25") (pintype "passive"))
      (node (ref "U4") (pin "30") (pinfunction "RSVD_30") (pintype "passive"))
      (node (ref "U4") (pin "33") (pinfunction "PGND_33") (pintype "passive"))
      (node (ref "U4") (pin "37") (pinfunction "AGND_2_37") (pintype "passive"))
      (node (ref "U4") (pin "38") (pinfunction "PLL_MODE0_38") (pintype "input"))
      (node (ref "U4") (pin "42") (pinfunction "AGND_42") (pintype "passive"))
      (node (ref "X1") (pin "10") (pinfunction "KL_10") (pintype "passive"))
      (node (ref "X1") (pin "12") (pinfunction "KL_12") (pintype "passive"))
      (node (ref "X1") (pin "14") (pinfunction "KL_14") (pintype "passive"))
      (node (ref "X1") (pin "16") (pinfunction "KL_16") (pintype "passive"))
      (node (ref "X1") (pin "18") (pinfunction "KL_18") (pintype "passive"))
      (node (ref "X1") (pin "20") (pinfunction "KL_20") (pintype "passive"))
      (node (ref "X1") (pin "4") (pinfunction "KL_4") (pintype "passive"))
      (node (ref "X1") (pin "6") (pinfunction "KL_6") (pintype "passive"))
      (node (ref "X1") (pin "8") (pinfunction "KL_8") (pintype "passive"))
      (node (ref "X2") (pin "10") (pinfunction "KL_10") (pintype "passive"))
      (node (ref "Y1") (pin "P$2") (pinfunction "GND_P$2") (pintype "power_in"))
    )
    (net (code "14") (name "MCLKI") (class "Default")
      (node (ref "R23") (pin "2") (pinfunction "2_2") (pintype "passive"))
      (node (ref "U3") (pin "32") (pinfunction "MCLKI_32") (pintype "input"))
      (node (ref "U4") (pin "32") (pinfunction "MCLKI_32") (pintype "input"))
    )
    (net (code "15") (name "MP1_1") (class "Default")
      (node (ref "SV1") (pin "1") (pinfunction "1_1") (pintype "passive"))
      (node (ref "U3") (pin "10") (pinfunction "MP1_10") (pintype "bidirectional"))
    )
    (net (code "16") (name "MP1_2") (class "Default")
      (node (ref "SV2") (pin "1") (pinfunction "1_1") (pintype "passive"))
      (node (ref "U4") (pin "10") (pinfunction "MP1_10") (pintype "bidirectional"))
    )
    (net (code "17") (name "MP2_1") (class "Default")
      (node (ref "SV1") (pin "2") (pinfunction "2_2") (pintype "passive"))
      (node (ref "U3") (pin "29") (pinfunction "MP2_29") (pintype "bidirectional"))
    )
    (net (code "18") (name "MP2_2") (class "Default")
      (node (ref "SV2") (pin "2") (pinfunction "2_2") (pintype "passive"))
      (node (ref "U4") (pin "29") (pinfunction "MP2_29") (pintype "bidirectional"))
    )
    (net (code "19") (name "MP3_1") (class "Default")
      (node (ref "SV1") (pin "3") (pinfunction "3_3") (pintype "passive"))
      (node (ref "U3") (pin "28") (pinfunction "MP3_28") (pintype "bidirectional"))
    )
    (net (code "20") (name "MP3_2") (class "Default")
      (node (ref "SV2") (pin "3") (pinfunction "3_3") (pintype "passive"))
      (node (ref "U4") (pin "28") (pinfunction "MP3_28") (pintype "bidirectional"))
    )
    (net (code "21") (name "MP7_1") (class "Default")
      (node (ref "SV1") (pin "4") (pinfunction "4_4") (pintype "passive"))
      (node (ref "U3") (pin "14") (pinfunction "MP7_14") (pintype "bidirectional"))
    )
    (net (code "22") (name "MP7_2") (class "Default")
      (node (ref "SV2") (pin "4") (pinfunction "4_4") (pintype "passive"))
      (node (ref "U4") (pin "14") (pinfunction "MP7_14") (pintype "bidirectional"))
    )
    (net (code "23") (name "MP8_1") (class "Default")
      (node (ref "SV1") (pin "5") (pinfunction "5_5") (pintype "passive"))
      (node (ref "U3") (pin "27") (pinfunction "MP8_27") (pintype "bidirectional"))
    )
    (net (code "24") (name "MP8_2") (class "Default")
      (node (ref "SV2") (pin "5") (pinfunction "5_5") (pintype "passive"))
      (node (ref "U4") (pin "27") (pinfunction "MP8_27") (pintype "bidirectional"))
    )
    (net (code "25") (name "MP9_1") (class "Default")
      (node (ref "SV1") (pin "6") (pinfunction "6_6") (pintype "passive"))
      (node (ref "U3") (pin "26") (pinfunction "MP9_26") (pintype "bidirectional"))
    )
    (net (code "26") (name "MP9_2") (class "Default")
      (node (ref "SV2") (pin "6") (pinfunction "6_6") (pintype "passive"))
      (node (ref "U4") (pin "26") (pinfunction "MP9_26") (pintype "bidirectional"))
    )
    (net (code "27") (name "Net-(C9-Pad-)") (class "Default")
      (node (ref "C9") (pin "-") (pinfunction "-_-") (pintype "passive"))
      (node (ref "R5") (pin "1") (pinfunction "1_1") (pintype "passive"))
    )
    (net (code "28") (name "Net-(C10-Pad1)") (class "Default")
      (node (ref "C10") (pin "1") (pinfunction "1_1") (pintype "passive"))
      (node (ref "R6") (pin "1") (pinfunction "1_1") (pintype "passive"))
    )
    (net (code "29") (name "Net-(C10-Pad2)") (class "Default")
      (node (ref "C10") (pin "2") (pinfunction "2_2") (pintype "passive"))
      (node (ref "C27") (pin "1") (pinfunction "1_1") (pintype "passive"))
      (node (ref "L1") (pin "1") (pinfunction "1_1") (pintype "passive"))
      (node (ref "R10") (pin "2") (pinfunction "2_2") (pintype "passive"))
    )
    (net (code "30") (name "Net-(C23-Pad-)") (class "Default")
      (node (ref "C23") (pin "-") (pinfunction "-_-") (pintype "passive"))
      (node (ref "R7") (pin "1") (pinfunction "1_1") (pintype "passive"))
    )
    (net (code "31") (name "Net-(C24-Pad2)") (class "Default")
      (node (ref "C24") (pin "2") (pinfunction "2_2") (pintype "passive"))
      (node (ref "R13") (pin "2") (pinfunction "2_2") (pintype "passive"))
    )
    (net (code "32") (name "Net-(C26-Pad1)") (class "Default")
      (node (ref "C26") (pin "1") (pinfunction "1_1") (pintype "passive"))
      (node (ref "R8") (pin "1") (pinfunction "1_1") (pintype "passive"))
    )
    (net (code "33") (name "Net-(C26-Pad2)") (class "Default")
      (node (ref "C26") (pin "2") (pinfunction "2_2") (pintype "passive"))
      (node (ref "C28") (pin "1") (pinfunction "1_1") (pintype "passive"))
      (node (ref "L2") (pin "1") (pinfunction "1_1") (pintype "passive"))
      (node (ref "R11") (pin "2") (pinfunction "2_2") (pintype "passive"))
    )
    (net (code "34") (name "Net-(C29-Pad-)") (class "Default")
      (node (ref "C29") (pin "-") (pinfunction "-_-") (pintype "passive"))
      (node (ref "R9") (pin "1") (pinfunction "1_1") (pintype "passive"))
    )
    (net (code "35") (name "Net-(C30-Pad-)") (class "Default")
      (node (ref "C30") (pin "-") (pinfunction "-_-") (pintype "passive"))
      (node (ref "R14") (pin "1") (pinfunction "1_1") (pintype "passive"))
    )
    (net (code "36") (name "Net-(C31-Pad1)") (class "Default")
      (node (ref "C31") (pin "1") (pinfunction "1_1") (pintype "passive"))
      (node (ref "J5") (pin "2") (pinfunction "2_2") (pintype "power_in"))
      (node (ref "R14") (pin "2") (pinfunction "2_2") (pintype "passive"))
      (node (ref "R15") (pin "2") (pinfunction "2_2") (pintype "passive"))
    )
    (net (code "37") (name "Net-(C32-Pad1)") (class "Default")
      (node (ref "C32") (pin "1") (pinfunction "1_1") (pintype "passive"))
      (node (ref "J5") (pin "3") (pinfunction "3_3") (pintype "power_in"))
      (node (ref "R16") (pin "2") (pinfunction "2_2") (pintype "passive"))
      (node (ref "R9") (pin "2") (pinfunction "2_2") (pintype "passive"))
    )
    (net (code "38") (name "Net-(C33-Pad1)") (class "Default")
      (node (ref "C33") (pin "1") (pinfunction "1_1") (pintype "passive"))
      (node (ref "J2") (pin "2") (pinfunction "2_2") (pintype "power_in"))
      (node (ref "R17") (pin "2") (pinfunction "2_2") (pintype "passive"))
      (node (ref "R7") (pin "2") (pinfunction "2_2") (pintype "passive"))
    )
    (net (code "39") (name "Net-(C34-Pad1)") (class "Default")
      (node (ref "C34") (pin "1") (pinfunction "1_1") (pintype "passive"))
      (node (ref "J2") (pin "3") (pinfunction "3_3") (pintype "power_in"))
      (node (ref "R18") (pin "2") (pinfunction "2_2") (pintype "passive"))
      (node (ref "R5") (pin "2") (pinfunction "2_2") (pintype "passive"))
    )
    (net (code "40") (name "Net-(C39-Pad-)") (class "Default")
      (node (ref "C39") (pin "-") (pinfunction "-_-") (pintype "passive"))
      (node (ref "R25") (pin "1") (pinfunction "1_1") (pintype "passive"))
    )
    (net (code "41") (name "Net-(C40-Pad1)") (class "Default")
      (node (ref "C40") (pin "1") (pinfunction "1_1") (pintype "passive"))
      (node (ref "R26") (pin "1") (pinfunction "1_1") (pintype "passive"))
    )
    (net (code "42") (name "Net-(C40-Pad2)") (class "Default")
      (node (ref "C40") (pin "2") (pinfunction "2_2") (pintype "passive"))
      (node (ref "C57") (pin "1") (pinfunction "1_1") (pintype "passive"))
      (node (ref "L3") (pin "1") (pinfunction "1_1") (pintype "passive"))
      (node (ref "R30") (pin "2") (pinfunction "2_2") (pintype "passive"))
    )
    (net (code "43") (name "Net-(C53-Pad-)") (class "Default")
      (node (ref "C53") (pin "-") (pinfunction "-_-") (pintype "passive"))
      (node (ref "R27") (pin "1") (pinfunction "1_1") (pintype "passive"))
    )
    (net (code "44") (name "Net-(C54-Pad2)") (class "Default")
      (node (ref "C54") (pin "2") (pinfunction "2_2") (pintype "passive"))
      (node (ref "R33") (pin "2") (pinfunction "2_2") (pintype "passive"))
    )
    (net (code "45") (name "Net-(C56-Pad1)") (class "Default")
      (node (ref "C56") (pin "1") (pinfunction "1_1") (pintype "passive"))
      (node (ref "R28") (pin "1") (pinfunction "1_1") (pintype "passive"))
    )
    (net (code "46") (name "Net-(C56-Pad2)") (class "Default")
      (node (ref "C56") (pin "2") (pinfunction "2_2") (pintype "passive"))
      (node (ref "C58") (pin "1") (pinfunction "1_1") (pintype "passive"))
      (node (ref "L4") (pin "1") (pinfunction "1_1") (pintype "passive"))
      (node (ref "R31") (pin "2") (pinfunction "2_2") (pintype "passive"))
    )
    (net (code "47") (name "Net-(C59-Pad-)") (class "Default")
      (node (ref "C59") (pin "-") (pinfunction "-_-") (pintype "passive"))
      (node (ref "R29") (pin "1") (pinfunction "1_1") (pintype "passive"))
    )
    (net (code "48") (name "Net-(C60-Pad-)") (class "Default")
      (node (ref "C60") (pin "-") (pinfunction "-_-") (pintype "passive"))
      (node (ref "R34") (pin "1") (pinfunction "1_1") (pintype "passive"))
    )
    (net (code "49") (name "Net-(C61-Pad1)") (class "Default")
      (node (ref "C61") (pin "1") (pinfunction "1_1") (pintype "passive"))
      (node (ref "J9") (pin "2") (pinfunction "2_2") (pintype "power_in"))
      (node (ref "R34") (pin "2") (pinfunction "2_2") (pintype "passive"))
      (node (ref "R35") (pin "2") (pinfunction "2_2") (pintype "passive"))
    )
    (net (code "50") (name "Net-(C62-Pad1)") (class "Default")
      (node (ref "C62") (pin "1") (pinfunction "1_1") (pintype "passive"))
      (node (ref "J9") (pin "3") (pinfunction "3_3") (pintype "power_in"))
      (node (ref "R29") (pin "2") (pinfunction "2_2") (pintype "passive"))
      (node (ref "R36") (pin "2") (pinfunction "2_2") (pintype "passive"))
    )
    (net (code "51") (name "Net-(C63-Pad1)") (class "Default")
      (node (ref "C63") (pin "1") (pinfunction "1_1") (pintype "passive"))
      (node (ref "J6") (pin "2") (pinfunction "2_2") (pintype "power_in"))
      (node (ref "R27") (pin "2") (pinfunction "2_2") (pintype "passive"))
      (node (ref "R37") (pin "2") (pinfunction "2_2") (pintype "passive"))
    )
    (net (code "52") (name "Net-(C64-Pad1)") (class "Default")
      (node (ref "C64") (pin "1") (pinfunction "1_1") (pintype "passive"))
      (node (ref "J6") (pin "3") (pinfunction "3_3") (pintype "power_in"))
      (node (ref "R25") (pin "2") (pinfunction "2_2") (pintype "passive"))
      (node (ref "R38") (pin "2") (pinfunction "2_2") (pintype "passive"))
    )
    (net (code "53") (name "Net-(J3-Pad2)") (class "Default")
      (node (ref "J3") (pin "2") (pinfunction "2_2") (pintype "bidirectional"))
      (node (ref "L1") (pin "2") (pinfunction "2_2") (pintype "passive"))
    )
    (net (code "54") (name "Net-(J4-Pad2)") (class "Default")
      (node (ref "J4") (pin "2") (pinfunction "2_2") (pintype "bidirectional"))
      (node (ref "L2") (pin "2") (pinfunction "2_2") (pintype "passive"))
    )
    (net (code "55") (name "Net-(J7-Pad2)") (class "Default")
      (node (ref "J7") (pin "2") (pinfunction "2_2") (pintype "bidirectional"))
      (node (ref "L3") (pin "2") (pinfunction "2_2") (pintype "passive"))
    )
    (net (code "56") (name "Net-(J8-Pad2)") (class "Default")
      (node (ref "J8") (pin "2") (pinfunction "2_2") (pintype "bidirectional"))
      (node (ref "L4") (pin "2") (pinfunction "2_2") (pintype "passive"))
    )
    (net (code "57") (name "Net-(LED1-PadA)") (class "Default")
      (node (ref "LED1") (pin "A") (pinfunction "A_A") (pintype "passive"))
      (node (ref "R2") (pin "1") (pinfunction "1_1") (pintype "passive"))
    )
    (net (code "58") (name "Net-(LED2-PadA)") (class "Default")
      (node (ref "LED2") (pin "A") (pinfunction "A_A") (pintype "passive"))
      (node (ref "R43") (pin "1") (pinfunction "1_1") (pintype "passive"))
    )
    (net (code "59") (name "Net-(T1-B)") (class "Default")
      (node (ref "R3") (pin "1") (pinfunction "1_1") (pintype "passive"))
      (node (ref "T1") (pin "3") (pinfunction "B_3") (pintype "passive"))
      (node (ref "U3") (pin "17") (pinfunction "VDRIVE_17") (pintype "output"))
    )
    (net (code "60") (name "Net-(T1-C)") (class "Default")
      (node (ref "C5") (pin "1") (pinfunction "1_1") (pintype "passive"))
      (node (ref "C6") (pin "+") (pinfunction "+_+") (pintype "passive"))
      (node (ref "C7") (pin "1") (pinfunction "1_1") (pintype "passive"))
      (node (ref "T1") (pin "1") (pinfunction "C_1") (pintype "passive"))
      (node (ref "U3") (pin "13") (pinfunction "DVDD_2_13") (pintype "power_in"))
      (node (ref "U3") (pin "24") (pinfunction "DVDD_24") (pintype "power_in"))
    )
    (net (code "61") (name "Net-(T2-B)") (class "Default")
      (node (ref "R24") (pin "1") (pinfunction "1_1") (pintype "passive"))
      (node (ref "T2") (pin "3") (pinfunction "B_3") (pintype "passive"))
      (node (ref "U4") (pin "17") (pinfunction "VDRIVE_17") (pintype "output"))
    )
    (net (code "62") (name "Net-(T2-C)") (class "Default")
      (node (ref "C36") (pin "1") (pinfunction "1_1") (pintype "passive"))
      (node (ref "C37") (pin "+") (pinfunction "+_+") (pintype "passive"))
      (node (ref "C38") (pin "1") (pinfunction "1_1") (pintype "passive"))
      (node (ref "T2") (pin "1") (pinfunction "C_1") (pintype "passive"))
      (node (ref "U4") (pin "13") (pinfunction "DVDD_2_13") (pintype "power_in"))
      (node (ref "U4") (pin "24") (pinfunction "DVDD_24") (pintype "power_in"))
    )
    (net (code "63") (name "Net-(U3A-ADC_RES)") (class "Default")
      (node (ref "R12") (pin "2") (pinfunction "2_2") (pintype "passive"))
      (node (ref "U3") (pin "3") (pinfunction "ADC_RES_3") (pintype "input"))
    )
    (net (code "64") (name "Net-(U3B-CM)") (class "Default")
      (node (ref "C21") (pin "1") (pinfunction "1_1") (pintype "passive"))
      (node (ref "C22") (pin "1") (pinfunction "1_1") (pintype "passive"))
      (node (ref "U3") (pin "40") (pinfunction "CM_40") (pintype "output"))
    )
    (net (code "65") (name "Net-(U3B-FILTA)") (class "Default")
      (node (ref "C17") (pin "1") (pinfunction "1_1") (pintype "passive"))
      (node (ref "C18") (pin "1") (pinfunction "1_1") (pintype "passive"))
      (node (ref "U3") (pin "47") (pinfunction "FILTA_47") (pintype "output"))
    )
    (net (code "66") (name "Net-(U3B-FILTD)") (class "Default")
      (node (ref "C19") (pin "1") (pinfunction "1_1") (pintype "passive"))
      (node (ref "C20") (pin "1") (pinfunction "1_1") (pintype "passive"))
      (node (ref "U3") (pin "41") (pinfunction "FILTD_41") (pintype "output"))
    )
    (net (code "67") (name "Net-(U3B-PLL_LF)") (class "Default")
      (node (ref "C24") (pin "1") (pinfunction "1_1") (pintype "passive"))
      (node (ref "C25") (pin "1") (pinfunction "1_1") (pintype "passive"))
      (node (ref "U3") (pin "35") (pinfunction "PLL_LF_35") (pintype "output"))
    )
    (net (code "68") (name "Net-(U4A-ADC_RES)") (class "Default")
      (node (ref "R32") (pin "2") (pinfunction "2_2") (pintype "passive"))
      (node (ref "U4") (pin "3") (pinfunction "ADC_RES_3") (pintype "input"))
    )
    (net (code "69") (name "Net-(U4B-CM)") (class "Default")
      (node (ref "C51") (pin "1") (pinfunction "1_1") (pintype "passive"))
      (node (ref "C52") (pin "1") (pinfunction "1_1") (pintype "passive"))
      (node (ref "U4") (pin "40") (pinfunction "CM_40") (pintype "output"))
    )
    (net (code "70") (name "Net-(U4B-FILTA)") (class "Default")
      (node (ref "C47") (pin "1") (pinfunction "1_1") (pintype "passive"))
      (node (ref "C48") (pin "1") (pinfunction "1_1") (pintype "passive"))
      (node (ref "U4") (pin "47") (pinfunction "FILTA_47") (pintype "output"))
    )
    (net (code "71") (name "Net-(U4B-FILTD)") (class "Default")
      (node (ref "C49") (pin "1") (pinfunction "1_1") (pintype "passive"))
      (node (ref "C50") (pin "1") (pinfunction "1_1") (pintype "passive"))
      (node (ref "U4") (pin "41") (pinfunction "FILTD_41") (pintype "output"))
    )
    (net (code "72") (name "Net-(U4B-PLL_LF)") (class "Default")
      (node (ref "C54") (pin "1") (pinfunction "1_1") (pintype "passive"))
      (node (ref "C55") (pin "1") (pinfunction "1_1") (pintype "passive"))
      (node (ref "U4") (pin "35") (pinfunction "PLL_LF_35") (pintype "output"))
    )
    (net (code "73") (name "Net-(Y1-OUT)") (class "Default")
      (node (ref "R23") (pin "1") (pinfunction "1_1") (pintype "passive"))
      (node (ref "Y1") (pin "P$3") (pinfunction "OUT_P$3") (pintype "output"))
    )
    (net (code "74") (name "OUT_BCLK_1") (class "Default")
      (node (ref "U3") (pin "19") (pinfunction "MP11_19") (pintype "bidirectional"))
      (node (ref "U4") (pin "9") (pinfunction "MP5_9") (pintype "bidirectional"))
    )
    (net (code "75") (name "OUT_BCLK_2") (class "Default")
      (node (ref "U3") (pin "9") (pinfunction "MP5_9") (pintype "bidirectional"))
      (node (ref "U4") (pin "19") (pinfunction "MP11_19") (pintype "bidirectional"))
    )
    (net (code "76") (name "OUT_LRCLK_1") (class "Default")
      (node (ref "U3") (pin "16") (pinfunction "MP10_16") (pintype "bidirectional"))
      (node (ref "U4") (pin "8") (pinfunction "MP4_8") (pintype "bidirectional"))
    )
    (net (code "77") (name "OUT_LRCLK_2") (class "Default")
      (node (ref "U3") (pin "8") (pinfunction "MP4_8") (pintype "bidirectional"))
      (node (ref "U4") (pin "16") (pinfunction "MP10_16") (pintype "bidirectional"))
    )
    (net (code "78") (name "PA0A") (class "Default")
      (node (ref "IC1") (pin "P$23") (pinfunction "PA0A_P$23") (pintype "bidirectional"))
      (node (ref "JP1") (pin "1") (pinfunction "1_1") (pintype "passive"))
    )
    (net (code "79") (name "PA1") (class "Default")
      (node (ref "IC1") (pin "P$12") (pinfunction "PA1_P$12") (pintype "bidirectional"))
      (node (ref "JP1") (pin "10") (pinfunction "10_10") (pintype "passive"))
      (node (ref "R2") (pin "2") (pinfunction "2_2") (pintype "passive"))
    )
    (net (code "80") (name "PB11") (class "Default")
      (node (ref "IC1") (pin "P$15") (pinfunction "PB11_P$15") (pintype "bidirectional"))
      (node (ref "JP1") (pin "5") (pinfunction "5_5") (pintype "passive"))
    )
    (net (code "81") (name "PB12") (class "Default")
      (node (ref "IC1") (pin "P$14") (pinfunction "PB12_P$14") (pintype "bidirectional"))
      (node (ref "JP1") (pin "8") (pinfunction "8_8") (pintype "passive"))
    )
    (net (code "82") (name "PB13") (class "Default")
      (node (ref "IC1") (pin "P$13") (pinfunction "PB13_P$13") (pintype "bidirectional"))
      (node (ref "JP1") (pin "7") (pinfunction "7_7") (pintype "passive"))
    )
    (net (code "83") (name "PC10A") (class "Default")
      (node (ref "IC1") (pin "P$22") (pinfunction "PC10A_P$22") (pintype "bidirectional"))
      (node (ref "JP1") (pin "4") (pinfunction "4_4") (pintype "passive"))
    )
    (net (code "84") (name "PC11A") (class "Default")
      (node (ref "IC1") (pin "P$21") (pinfunction "PC11A_P$21") (pintype "bidirectional"))
      (node (ref "JP1") (pin "3") (pinfunction "3_3") (pintype "passive"))
    )
    (net (code "85") (name "PD13A") (class "Default")
      (node (ref "IC1") (pin "P$11") (pinfunction "PD13A_P$11") (pintype "bidirectional"))
      (node (ref "JP1") (pin "9") (pinfunction "9_9") (pintype "passive"))
    )
    (net (code "86") (name "PD14") (class "Default")
      (node (ref "IC1") (pin "P$32") (pinfunction "PD14_P$32") (pintype "bidirectional"))
      (node (ref "JP1") (pin "6") (pinfunction "6_6") (pintype "passive"))
    )
    (net (code "87") (name "PD15A") (class "Default")
      (node (ref "IC1") (pin "P$24") (pinfunction "PD15A_P$24") (pintype "bidirectional"))
      (node (ref "JP1") (pin "2") (pinfunction "2_2") (pintype "passive"))
    )
    (net (code "88") (name "PSW") (class "Default")
      (node (ref "S1") (pin "2") (pinfunction "2_2") (pintype "bidirectional"))
      (node (ref "U1") (pin "1") (pinfunction "EN_1") (pintype "input"))
    )
    (net (code "89") (name "SCL") (class "Default")
      (node (ref "IC1") (pin "P$19") (pinfunction "PF2A_P$19") (pintype "bidirectional"))
      (node (ref "U3") (pin "23") (pinfunction "SCL/CCLK_23") (pintype "bidirectional"))
      (node (ref "U4") (pin "23") (pinfunction "SCL/CCLK_23") (pintype "bidirectional"))
      (node (ref "X2") (pin "1") (pinfunction "KL_1") (pintype "passive"))
    )
    (net (code "90") (name "SDA") (class "Default")
      (node (ref "IC1") (pin "P$20") (pinfunction "PF3A_P$20") (pintype "bidirectional"))
      (node (ref "U3") (pin "22") (pinfunction "SDA/COUT_22") (pintype "bidirectional"))
      (node (ref "U4") (pin "22") (pinfunction "SDA/COUT_22") (pintype "bidirectional"))
      (node (ref "X2") (pin "3") (pinfunction "KL_3") (pintype "passive"))
    )
    (net (code "91") (name "SELFBOOT_1") (class "Default")
      (node (ref "R22") (pin "2") (pinfunction "2_2") (pintype "passive"))
      (node (ref "U3") (pin "6") (pinfunction "SELFBOOT_6") (pintype "input"))
    )
    (net (code "92") (name "SELFBOOT_2") (class "Default")
      (node (ref "R42") (pin "2") (pinfunction "2_2") (pintype "passive"))
      (node (ref "U4") (pin "6") (pinfunction "SELFBOOT_6") (pintype "input"))
    )
    (net (code "93") (name "SWCLK") (class "Default")
      (node (ref "IC1") (pin "P$9") (pinfunction "PF1_P$9") (pintype "bidirectional"))
      (node (ref "X1") (pin "7") (pinfunction "KL_7") (pintype "passive"))
    )
    (net (code "94") (name "SWDIO") (class "Default")
      (node (ref "IC1") (pin "P$10") (pinfunction "PF0_P$10") (pintype "bidirectional"))
      (node (ref "X1") (pin "9") (pinfunction "KL_9") (pintype "passive"))
    )
    (net (code "95") (name "SWO") (class "Default")
      (node (ref "X1") (pin "13") (pinfunction "KL_13") (pintype "passive"))
    )
    (net (code "96") (name "TDM_OUT_1") (class "Default")
      (node (ref "U3") (pin "15") (pinfunction "MP6_15") (pintype "bidirectional"))
      (node (ref "U4") (pin "11") (pinfunction "MP0_11") (pintype "bidirectional"))
    )
    (net (code "97") (name "TDM_OUT_2") (class "Default")
      (node (ref "U3") (pin "11") (pinfunction "MP0_11") (pintype "bidirectional"))
      (node (ref "U4") (pin "15") (pinfunction "MP6_15") (pintype "bidirectional"))
    )
    (net (code "98") (name "VDD") (class "Default")
      (node (ref "C11") (pin "+") (pinfunction "+_+") (pintype "passive"))
      (node (ref "C12") (pin "1") (pinfunction "1_1") (pintype "passive"))
      (node (ref "C13") (pin "1") (pinfunction "1_1") (pintype "passive"))
      (node (ref "C14") (pin "1") (pinfunction "1_1") (pintype "passive"))
      (node (ref "C15") (pin "+") (pinfunction "+_+") (pintype "passive"))
      (node (ref "C16") (pin "1") (pinfunction "1_1") (pintype "passive"))
      (node (ref "C2") (pin "+") (pinfunction "+_+") (pintype "passive"))
      (node (ref "C25") (pin "2") (pinfunction "2_2") (pintype "passive"))
      (node (ref "C3") (pin "1") (pinfunction "1_1") (pintype "passive"))
      (node (ref "C35") (pin "1") (pinfunction "1_1") (pintype "passive"))
      (node (ref "C4") (pin "1") (pinfunction "1_1") (pintype "passive"))
      (node (ref "C41") (pin "+") (pinfunction "+_+") (pintype "passive"))
      (node (ref "C42") (pin "1") (pinfunction "1_1") (pintype "passive"))
      (node (ref "C43") (pin "1") (pinfunction "1_1") (pintype "passive"))
      (node (ref "C44") (pin "1") (pinfunction "1_1") (pintype "passive"))
      (node (ref "C45") (pin "+") (pinfunction "+_+") (pintype "passive"))
      (node (ref "C46") (pin "1") (pinfunction "1_1") (pintype "passive"))
      (node (ref "C55") (pin "2") (pinfunction "2_2") (pintype "passive"))
      (node (ref "C8") (pin "1") (pinfunction "1_1") (pintype "passive"))
      (node (ref "IC1") (pin "P$17") (pinfunction "VDD1_P$17") (pintype "power_in"))
      (node (ref "IC1") (pin "P$8") (pinfunction "VDD0_P$8") (pintype "power_in"))
      (node (ref "JP2") (pin "1") (pinfunction "1_1") (pintype "passive"))
      (node (ref "JP2") (pin "11") (pinfunction "11_11") (pintype "passive"))
      (node (ref "JP2") (pin "3") (pinfunction "3_3") (pintype "passive"))
      (node (ref "JP2") (pin "5") (pinfunction "5_5") (pintype "passive"))
      (node (ref "JP2") (pin "7") (pinfunction "7_7") (pintype "passive"))
      (node (ref "JP2") (pin "9") (pinfunction "9_9") (pintype "passive"))
      (node (ref "JP3") (pin "1") (pinfunction "1_1") (pintype "passive"))
      (node (ref "JP3") (pin "11") (pinfunction "11_11") (pintype "passive"))
      (node (ref "JP3") (pin "3") (pinfunction "3_3") (pintype "passive"))
      (node (ref "JP3") (pin "5") (pinfunction "5_5") (pintype "passive"))
      (node (ref "JP3") (pin "7") (pinfunction "7_7") (pintype "passive"))
      (node (ref "JP3") (pin "9") (pinfunction "9_9") (pintype "passive"))
      (node (ref "R13") (pin "1") (pinfunction "1_1") (pintype "passive"))
      (node (ref "R19") (pin "2") (pinfunction "2_2") (pintype "passive"))
      (node (ref "R24") (pin "2") (pinfunction "2_2") (pintype "passive"))
      (node (ref "R3") (pin "2") (pinfunction "2_2") (pintype "passive"))
      (node (ref "R33") (pin "1") (pinfunction "1_1") (pintype "passive"))
      (node (ref "R39") (pin "2") (pinfunction "2_2") (pintype "passive"))
      (node (ref "R43") (pin "2") (pinfunction "2_2") (pintype "passive"))
      (node (ref "SW1") (pin "3") (pinfunction "3_3") (pintype "passive"))
      (node (ref "SW1") (pin "4") (pinfunction "4_4") (pintype "passive"))
      (node (ref "SW2") (pin "3") (pinfunction "3_3") (pintype "passive"))
      (node (ref "SW2") (pin "4") (pinfunction "4_4") (pintype "passive"))
      (node (ref "T1") (pin "2") (pinfunction "E_2") (pintype "passive"))
      (node (ref "T2") (pin "2") (pinfunction "E_2") (pintype "passive"))
      (node (ref "U1") (pin "3") (pinfunction "OUT_3") (pintype "output"))
      (node (ref "U2") (pin "4") (pinfunction "VCC_4") (pintype "power_in"))
      (node (ref "U3") (pin "18") (pinfunction "IOVDD_18") (pintype "power_in"))
      (node (ref "U3") (pin "34") (pinfunction "PVDD_34") (pintype "power_in"))
      (node (ref "U3") (pin "36") (pinfunction "AVDD_2_36") (pintype "power_in"))
      (node (ref "U3") (pin "39") (pinfunction "PLL_MODE1_39") (pintype "input"))
      (node (ref "U3") (pin "48") (pinfunction "AVDD_48") (pintype "power_in"))
      (node (ref "U4") (pin "18") (pinfunction "IOVDD_18") (pintype "power_in"))
      (node (ref "U4") (pin "34") (pinfunction "PVDD_34") (pintype "power_in"))
      (node (ref "U4") (pin "36") (pinfunction "AVDD_2_36") (pintype "power_in"))
      (node (ref "U4") (pin "39") (pinfunction "PLL_MODE1_39") (pintype "input"))
      (node (ref "U4") (pin "48") (pinfunction "AVDD_48") (pintype "power_in"))
      (node (ref "X1") (pin "1") (pinfunction "KL_1") (pintype "passive"))
      (node (ref "Y1") (pin "P$4") (pinfunction "VCC_P$4") (pintype "power_in"))
    )
    (net (code "99") (name "VIN") (class "Default")
      (node (ref "C1") (pin "1") (pinfunction "1_1") (pintype "passive"))
      (node (ref "J1") (pin "PWR") (pinfunction "PWR_PWR") (pintype "bidirectional"))
      (node (ref "R1") (pin "1") (pinfunction "1_1") (pintype "passive"))
      (node (ref "S1") (pin "1") (pinfunction "1_1") (pintype "bidirectional"))
      (node (ref "U1") (pin "2") (pinfunction "IN_2") (pintype "input"))
    )
    (net (code "100") (name "VOUT0_1") (class "Default")
      (node (ref "C23") (pin "+") (pinfunction "+_+") (pintype "passive"))
      (node (ref "U3") (pin "46") (pinfunction "VOUT0_46") (pintype "output"))
    )
    (net (code "101") (name "VOUT0_2") (class "Default")
      (node (ref "C53") (pin "+") (pinfunction "+_+") (pintype "passive"))
      (node (ref "U4") (pin "46") (pinfunction "VOUT0_46") (pintype "output"))
    )
    (net (code "102") (name "VOUT1_1") (class "Default")
      (node (ref "C9") (pin "+") (pinfunction "+_+") (pintype "passive"))
      (node (ref "U3") (pin "45") (pinfunction "VOUT1_45") (pintype "output"))
    )
    (net (code "103") (name "VOUT1_2") (class "Default")
      (node (ref "C39") (pin "+") (pinfunction "+_+") (pintype "passive"))
      (node (ref "U4") (pin "45") (pinfunction "VOUT1_45") (pintype "output"))
    )
    (net (code "104") (name "VOUT2_1") (class "Default")
      (node (ref "C30") (pin "+") (pinfunction "+_+") (pintype "passive"))
      (node (ref "U3") (pin "44") (pinfunction "VOUT2_44") (pintype "output"))
    )
    (net (code "105") (name "VOUT2_2") (class "Default")
      (node (ref "C60") (pin "+") (pinfunction "+_+") (pintype "passive"))
      (node (ref "U4") (pin "44") (pinfunction "VOUT2_44") (pintype "output"))
    )
    (net (code "106") (name "VOUT3_1") (class "Default")
      (node (ref "C29") (pin "+") (pinfunction "+_+") (pintype "passive"))
      (node (ref "U3") (pin "43") (pinfunction "VOUT3_43") (pintype "output"))
    )
    (net (code "107") (name "VOUT3_2") (class "Default")
      (node (ref "C59") (pin "+") (pinfunction "+_+") (pintype "passive"))
      (node (ref "U4") (pin "43") (pinfunction "VOUT3_43") (pintype "output"))
    )
    (net (code "108") (name "WP_1") (class "Default")
      (node (ref "R19") (pin "1") (pinfunction "1_1") (pintype "passive"))
      (node (ref "U3") (pin "21") (pinfunction "CLATCH/WP_21") (pintype "bidirectional"))
    )
    (net (code "109") (name "WP_2") (class "Default")
      (node (ref "R39") (pin "1") (pinfunction "1_1") (pintype "passive"))
      (node (ref "U4") (pin "21") (pinfunction "CLATCH/WP_21") (pintype "bidirectional"))
    )
    (net (code "110") (name "unconnected-(IC1-NC0-PadP$16)") (class "Default")
      (node (ref "IC1") (pin "P$16") (pinfunction "NC0_P$16") (pintype "no_connect"))
    )
    (net (code "111") (name "unconnected-(IC1-NC1-PadP$35)") (class "Default")
      (node (ref "IC1") (pin "P$35") (pinfunction "NC1_P$35") (pintype "no_connect"))
    )
    (net (code "112") (name "unconnected-(IC1-PA0B-PadP$27)") (class "Default")
      (node (ref "IC1") (pin "P$27") (pinfunction "PA0B_P$27") (pintype "bidirectional"))
    )
    (net (code "113") (name "unconnected-(IC1-PC10B-PadP$29)") (class "Default")
      (node (ref "IC1") (pin "P$29") (pinfunction "PC10B_P$29") (pintype "bidirectional"))
    )
    (net (code "114") (name "unconnected-(IC1-PC11B-PadP$28)") (class "Default")
      (node (ref "IC1") (pin "P$28") (pinfunction "PC11B_P$28") (pintype "bidirectional"))
    )
    (net (code "115") (name "unconnected-(IC1-PD13B-PadP$33)") (class "Default")
      (node (ref "IC1") (pin "P$33") (pinfunction "PD13B_P$33") (pintype "bidirectional"))
    )
    (net (code "116") (name "unconnected-(IC1-PD15B-PadP$26)") (class "Default")
      (node (ref "IC1") (pin "P$26") (pinfunction "PD15B_P$26") (pintype "bidirectional"))
    )
    (net (code "117") (name "unconnected-(IC1-PF2B-PadP$30)") (class "Default")
      (node (ref "IC1") (pin "P$30") (pinfunction "PF2B_P$30") (pintype "bidirectional"))
    )
    (net (code "118") (name "unconnected-(IC1-PF3B-PadP$31)") (class "Default")
      (node (ref "IC1") (pin "P$31") (pinfunction "PF3B_P$31") (pintype "bidirectional"))
    )
    (net (code "119") (name "unconnected-(U3B-OSCO-Pad31)") (class "Default")
      (node (ref "U3") (pin "31") (pinfunction "OSCO_31") (pintype "output"))
    )
    (net (code "120") (name "unconnected-(U4B-OSCO-Pad31)") (class "Default")
      (node (ref "U4") (pin "31") (pinfunction "OSCO_31") (pintype "output"))
    )
    (net (code "121") (name "unconnected-(X1C-KL-Pad11)") (class "Default")
      (node (ref "X1") (pin "11") (pinfunction "KL_11") (pintype "passive"))
    )
    (net (code "122") (name "unconnected-(X1I-KL-Pad17)") (class "Default")
      (node (ref "X1") (pin "17") (pinfunction "KL_17") (pintype "passive"))
    )
    (net (code "123") (name "unconnected-(X1L-KL-Pad2)") (class "Default")
      (node (ref "X1") (pin "2") (pinfunction "KL_2") (pintype "passive"))
    )
    (net (code "124") (name "unconnected-(X1N-KL-Pad3)") (class "Default")
      (node (ref "X1") (pin "3") (pinfunction "KL_3") (pintype "passive"))
    )
    (net (code "125") (name "unconnected-(X1P-KL-Pad5)") (class "Default")
      (node (ref "X1") (pin "5") (pinfunction "KL_5") (pintype "passive"))
    )
    (net (code "126") (name "unconnected-(X2C-KL-Pad2)") (class "Default")
      (node (ref "X2") (pin "2") (pinfunction "KL_2") (pintype "passive"))
    )
    (net (code "127") (name "unconnected-(X2E-KL-Pad4)") (class "Default")
      (node (ref "X2") (pin "4") (pinfunction "KL_4") (pintype "passive"))
    )
    (net (code "128") (name "unconnected-(X2F-KL-Pad5)") (class "Default")
      (node (ref "X2") (pin "5") (pinfunction "KL_5") (pintype "passive"))
    )
    (net (code "129") (name "unconnected-(X2H-KL-Pad7)") (class "Default")
      (node (ref "X2") (pin "7") (pinfunction "KL_7") (pintype "passive"))
    )
    (net (code "130") (name "unconnected-(X2I-KL-Pad8)") (class "Default")
      (node (ref "X2") (pin "8") (pinfunction "KL_8") (pintype "passive"))
    )
    (net (code "131") (name "unconnected-(X2J-KL-Pad9)") (class "Default")
      (node (ref "X2") (pin "9") (pinfunction "KL_9") (pintype "passive"))
    )
    (net (code "132") (name "unconnected-(Y1-ST-PadP$1)") (class "Default")
      (node (ref "Y1") (pin "P$1") (pinfunction "ST_P$1") (pintype "input"))
    )
  )
)
